# transmitter.net
KiCad netlist of a schematic drawn in EAGLE
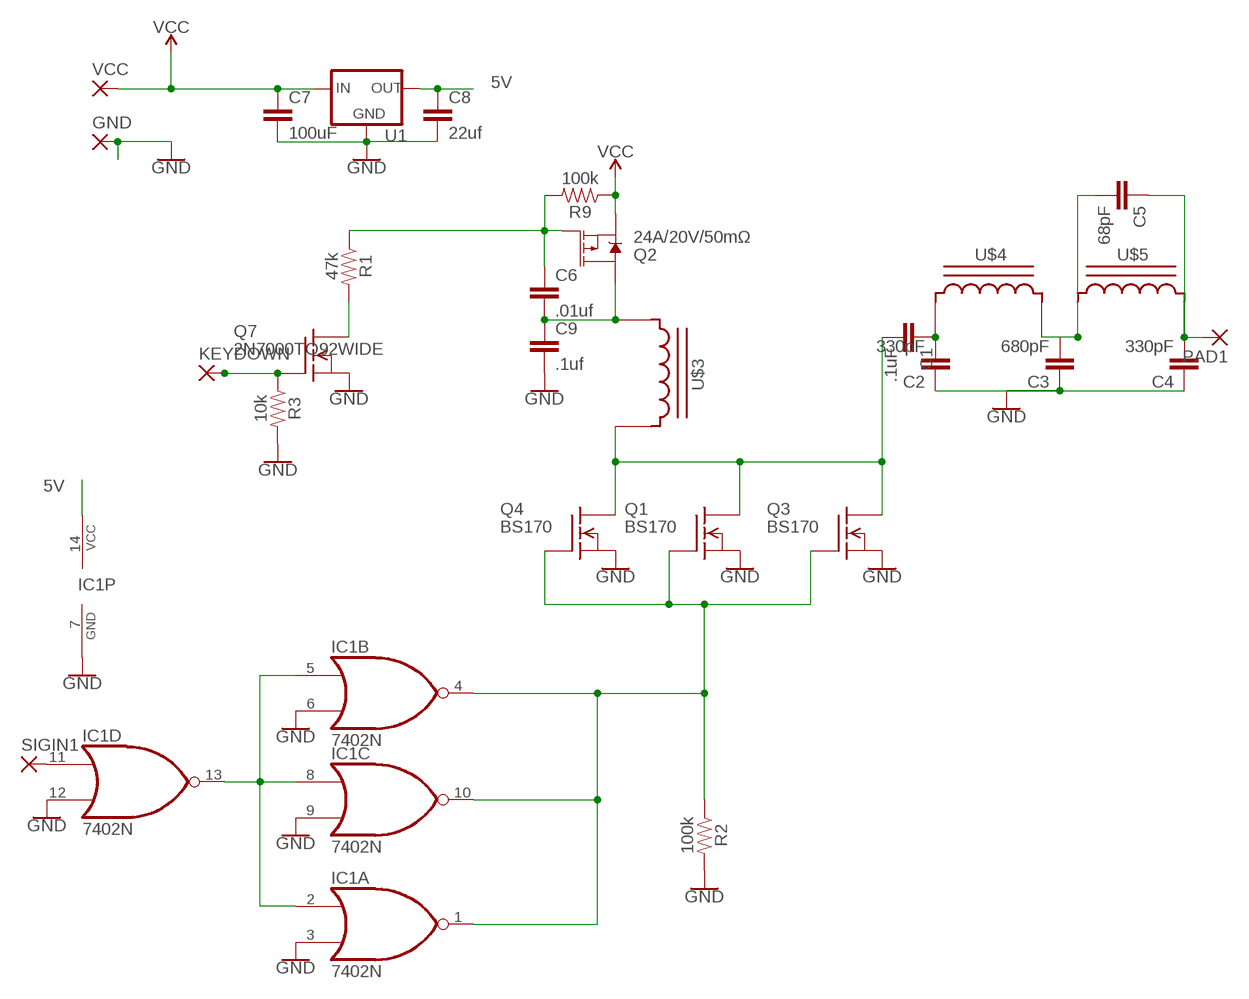
[diagram p0: schematic, sheet 1]

(export (version "E")
  (design (tool "Eeschema 10.0.6"))
  (components
    (comp (ref "C1")
      (value ".1uF")
      (footprint "eagle-import:C5B3.5")
      (libsource (lib "eagle-import") (part "C5/3.5"))
    )
    (comp (ref "C2")
      (value "330pF")
      (footprint "eagle-import:C5B3.5")
      (libsource (lib "eagle-import") (part "C5/3.5"))
    )
    (comp (ref "C3")
      (value "680pF")
      (footprint "eagle-import:C5B3.5")
      (libsource (lib "eagle-import") (part "C5/3.5"))
    )
    (comp (ref "C4")
      (value "330pF")
      (footprint "eagle-import:C5B3.5")
      (libsource (lib "eagle-import") (part "C5/3.5"))
    )
    (comp (ref "C5")
      (value "68pF")
      (footprint "eagle-import:C5B3.5")
      (libsource (lib "eagle-import") (part "C5/3.5"))
    )
    (comp (ref "C6")
      (value ".01uf")
      (footprint "eagle-import:C5B3.5")
      (libsource (lib "eagle-import") (part "C5/3.5"))
    )
    (comp (ref "C7")
      (value "100uF")
      (footprint "eagle-import:C5B3.5")
      (libsource (lib "eagle-import") (part "C5/3.5"))
    )
    (comp (ref "C8")
      (value "22uf")
      (footprint "eagle-import:C5B3.5")
      (libsource (lib "eagle-import") (part "C5/3.5"))
    )
    (comp (ref "C9")
      (value ".1uf")
      (footprint "eagle-import:C5B3.5")
      (libsource (lib "eagle-import") (part "C5/3.5"))
    )
    (comp (ref "GND")
      (value "3,17/1,1")
      (footprint "eagle-import:3,17_1,1")
      (libsource (lib "eagle-import") (part "3,17/1,1"))
    )
    (comp (ref "IC1")
      (value "7402N")
      (footprint "eagle-import:DIL14")
      (libsource (lib "eagle-import") (part "7402N"))
    )
    (comp (ref "KEYDOWN")
      (value "3,17/1,1")
      (footprint "eagle-import:3,17_1,1")
      (libsource (lib "eagle-import") (part "3,17/1,1"))
    )
    (comp (ref "PAD1")
      (value "3,17/1,1")
      (footprint "eagle-import:3,17_1,1")
      (libsource (lib "eagle-import") (part "3,17/1,1"))
    )
    (comp (ref "Q1")
      (value "BS170")
      (footprint "eagle-import:TO92")
      (libsource (lib "eagle-import") (part "BS170"))
    )
    (comp (ref "Q2")
      (value "24A/20V/50mΩ")
      (footprint "eagle-import:TO220V")
      (libsource (lib "eagle-import") (part "MOSFET_PCH-NDP6020P"))
    )
    (comp (ref "Q3")
      (value "BS170")
      (footprint "eagle-import:TO92")
      (libsource (lib "eagle-import") (part "BS170"))
    )
    (comp (ref "Q4")
      (value "BS170")
      (footprint "eagle-import:TO92")
      (libsource (lib "eagle-import") (part "BS170"))
    )
    (comp (ref "Q7")
      (value "2N7000TO92WIDE")
      (footprint "eagle-import:TO92")
      (libsource (lib "eagle-import") (part "2N7000TO92WIDE"))
    )
    (comp (ref "R1")
      (value "47k")
      (footprint "eagle-import:AXIAL-0.3")
      (libsource (lib "eagle-import") (part "1KOHM-HORIZ-1/4W-1%"))
    )
    (comp (ref "R2")
      (value "100k")
      (footprint "eagle-import:AXIAL-0.3")
      (libsource (lib "eagle-import") (part "1KOHM-HORIZ-1/4W-1%"))
    )
    (comp (ref "R3")
      (value "10k")
      (footprint "eagle-import:AXIAL-0.3")
      (libsource (lib "eagle-import") (part "1KOHM-HORIZ-1/4W-1%"))
    )
    (comp (ref "R9")
      (value "100k")
      (footprint "eagle-import:AXIAL-0.3")
      (libsource (lib "eagle-import") (part "1KOHM-HORIZ-1/4W-1%"))
    )
    (comp (ref "SIGIN1")
      (value "3,17/1,1")
      (footprint "eagle-import:3,17_1,1")
      (libsource (lib "eagle-import") (part "3,17/1,1"))
    )
    (comp (ref "U$3")
      (value "T50_INDUCTOR")
      (footprint "eagle-import:T50_INDUCTOR")
      (libsource (lib "eagle-import") (part "T50_INDUCTOR"))
    )
    (comp (ref "U$4")
      (value "T37_INDUCTOR")
      (footprint "eagle-import:T37_INDUCTOR")
      (libsource (lib "eagle-import") (part "T37_INDUCTOR"))
    )
    (comp (ref "U$5")
      (value "T37_INDUCTOR")
      (footprint "eagle-import:T37_INDUCTOR")
      (libsource (lib "eagle-import") (part "T37_INDUCTOR"))
    )
    (comp (ref "U1")
      (value "V_REG_78XXTO-92_UNTESTED")
      (footprint "eagle-import:TO-92")
      (libsource (lib "eagle-import") (part "V_REG_78XXTO-92_UNTESTED"))
    )
    (comp (ref "VCC")
      (value "3,17/1,1")
      (footprint "eagle-import:3,17_1,1")
      (libsource (lib "eagle-import") (part "3,17/1,1"))
    )
  )
  (nets
    (net (code "1") (name "/5V") (class "Default")
      (node (ref "C8") (pin "1") (pinfunction "1_1") (pintype "passive"))
      (node (ref "IC1") (pin "14") (pinfunction "VCC_14") (pintype "power_in"))
      (node (ref "U1") (pin "1") (pinfunction "OUT_1") (pintype "passive"))
    )
    (net (code "2") (name "GND") (class "Default")
      (node (ref "C2") (pin "1") (pinfunction "1_1") (pintype "passive"))
      (node (ref "C3") (pin "1") (pinfunction "1_1") (pintype "passive"))
      (node (ref "C4") (pin "1") (pinfunction "1_1") (pintype "passive"))
      (node (ref "C7") (pin "2") (pinfunction "2_2") (pintype "passive"))
      (node (ref "C8") (pin "2") (pinfunction "2_2") (pintype "passive"))
      (node (ref "C9") (pin "2") (pinfunction "2_2") (pintype "passive"))
      (node (ref "GND") (pin "1") (pinfunction "P_1") (pintype "passive"))
      (node (ref "IC1") (pin "12") (pinfunction "I1_12") (pintype "input"))
      (node (ref "IC1") (pin "3") (pinfunction "I1_3") (pintype "input"))
      (node (ref "IC1") (pin "6") (pinfunction "I1_6") (pintype "input"))
      (node (ref "IC1") (pin "7") (pinfunction "GND_7") (pintype "power_in"))
      (node (ref "IC1") (pin "9") (pinfunction "I1_9") (pintype "input"))
      (node (ref "Q1") (pin "1") (pinfunction "S_1") (pintype "passive"))
      (node (ref "Q3") (pin "1") (pinfunction "S_1") (pintype "passive"))
      (node (ref "Q4") (pin "1") (pinfunction "S_1") (pintype "passive"))
      (node (ref "Q7") (pin "1") (pinfunction "S_1") (pintype "passive"))
      (node (ref "R2") (pin "P$2") (pinfunction "2_P$2") (pintype "passive"))
      (node (ref "R3") (pin "P$2") (pinfunction "2_P$2") (pintype "passive"))
      (node (ref "U1") (pin "2") (pinfunction "GND_2") (pintype "input"))
    )
    (net (code "3") (name "Net-(C1-Pad1)") (class "Default")
      (node (ref "C1") (pin "1") (pinfunction "1_1") (pintype "passive"))
      (node (ref "C2") (pin "2") (pinfunction "2_2") (pintype "passive"))
      (node (ref "U$4") (pin "CB") (pinfunction "CB_CB") (pintype "bidirectional"))
    )
    (net (code "4") (name "Net-(C3-Pad2)") (class "Default")
      (node (ref "C3") (pin "2") (pinfunction "2_2") (pintype "passive"))
      (node (ref "C5") (pin "2") (pinfunction "2_2") (pintype "passive"))
      (node (ref "U$4") (pin "CA") (pinfunction "CA_CA") (pintype "bidirectional"))
      (node (ref "U$5") (pin "CB") (pinfunction "CB_CB") (pintype "bidirectional"))
    )
    (net (code "5") (name "Net-(IC1A-I0)") (class "Default")
      (node (ref "IC1") (pin "13") (pinfunction "O_13") (pintype "output"))
      (node (ref "IC1") (pin "2") (pinfunction "I0_2") (pintype "input"))
      (node (ref "IC1") (pin "5") (pinfunction "I0_5") (pintype "input"))
      (node (ref "IC1") (pin "8") (pinfunction "I0_8") (pintype "input"))
    )
    (net (code "6") (name "Net-(IC1A-O)") (class "Default")
      (node (ref "IC1") (pin "1") (pinfunction "O_1") (pintype "output"))
      (node (ref "IC1") (pin "10") (pinfunction "O_10") (pintype "output"))
      (node (ref "IC1") (pin "4") (pinfunction "O_4") (pintype "output"))
      (node (ref "Q1") (pin "2") (pinfunction "G_2") (pintype "passive"))
      (node (ref "Q3") (pin "2") (pinfunction "G_2") (pintype "passive"))
      (node (ref "Q4") (pin "2") (pinfunction "G_2") (pintype "passive"))
      (node (ref "R2") (pin "P$1") (pinfunction "1_P$1") (pintype "passive"))
    )
    (net (code "7") (name "Net-(IC1D-I0)") (class "Default")
      (node (ref "IC1") (pin "11") (pinfunction "I0_11") (pintype "input"))
      (node (ref "SIGIN1") (pin "1") (pinfunction "P_1") (pintype "passive"))
    )
    (net (code "8") (name "Net-(KEYDOWN-P)") (class "Default")
      (node (ref "KEYDOWN") (pin "1") (pinfunction "P_1") (pintype "passive"))
      (node (ref "Q7") (pin "2") (pinfunction "G_2") (pintype "passive"))
      (node (ref "R3") (pin "P$1") (pinfunction "1_P$1") (pintype "passive"))
    )
    (net (code "9") (name "Net-(PAD1-P)") (class "Default")
      (node (ref "C4") (pin "2") (pinfunction "2_2") (pintype "passive"))
      (node (ref "C5") (pin "1") (pinfunction "1_1") (pintype "passive"))
      (node (ref "PAD1") (pin "1") (pinfunction "P_1") (pintype "passive"))
      (node (ref "U$5") (pin "CA") (pinfunction "CA_CA") (pintype "bidirectional"))
    )
    (net (code "10") (name "Net-(Q1-D)") (class "Default")
      (node (ref "C1") (pin "2") (pinfunction "2_2") (pintype "passive"))
      (node (ref "Q1") (pin "3") (pinfunction "D_3") (pintype "passive"))
      (node (ref "Q3") (pin "3") (pinfunction "D_3") (pintype "passive"))
      (node (ref "Q4") (pin "3") (pinfunction "D_3") (pintype "passive"))
      (node (ref "U$3") (pin "CA") (pinfunction "CA_CA") (pintype "bidirectional"))
    )
    (net (code "11") (name "Net-(Q2-D)") (class "Default")
      (node (ref "C6") (pin "2") (pinfunction "2_2") (pintype "passive"))
      (node (ref "C9") (pin "1") (pinfunction "1_1") (pintype "passive"))
      (node (ref "Q2") (pin "2") (pinfunction "D_2") (pintype "bidirectional"))
      (node (ref "U$3") (pin "CB") (pinfunction "CB_CB") (pintype "bidirectional"))
    )
    (net (code "12") (name "Net-(Q2-G)") (class "Default")
      (node (ref "C6") (pin "1") (pinfunction "1_1") (pintype "passive"))
      (node (ref "Q2") (pin "1") (pinfunction "G_1") (pintype "bidirectional"))
      (node (ref "R1") (pin "P$1") (pinfunction "1_P$1") (pintype "passive"))
      (node (ref "R9") (pin "P$2") (pinfunction "2_P$2") (pintype "passive"))
    )
    (net (code "13") (name "Net-(Q7-D)") (class "Default")
      (node (ref "Q7") (pin "3") (pinfunction "D_3") (pintype "passive"))
      (node (ref "R1") (pin "P$2") (pinfunction "2_P$2") (pintype "passive"))
    )
    (net (code "14") (name "VCC") (class "Default")
      (node (ref "C7") (pin "1") (pinfunction "1_1") (pintype "passive"))
      (node (ref "Q2") (pin "3") (pinfunction "S_3") (pintype "bidirectional"))
      (node (ref "R9") (pin "P$1") (pinfunction "1_P$1") (pintype "passive"))
      (node (ref "U1") (pin "3") (pinfunction "IN_3") (pintype "input"))
      (node (ref "VCC") (pin "1") (pinfunction "P_1") (pintype "passive"))
    )
  )
)
